# ttl-nixie-clock.net
KiCad netlist of a schematic drawn in EAGLE
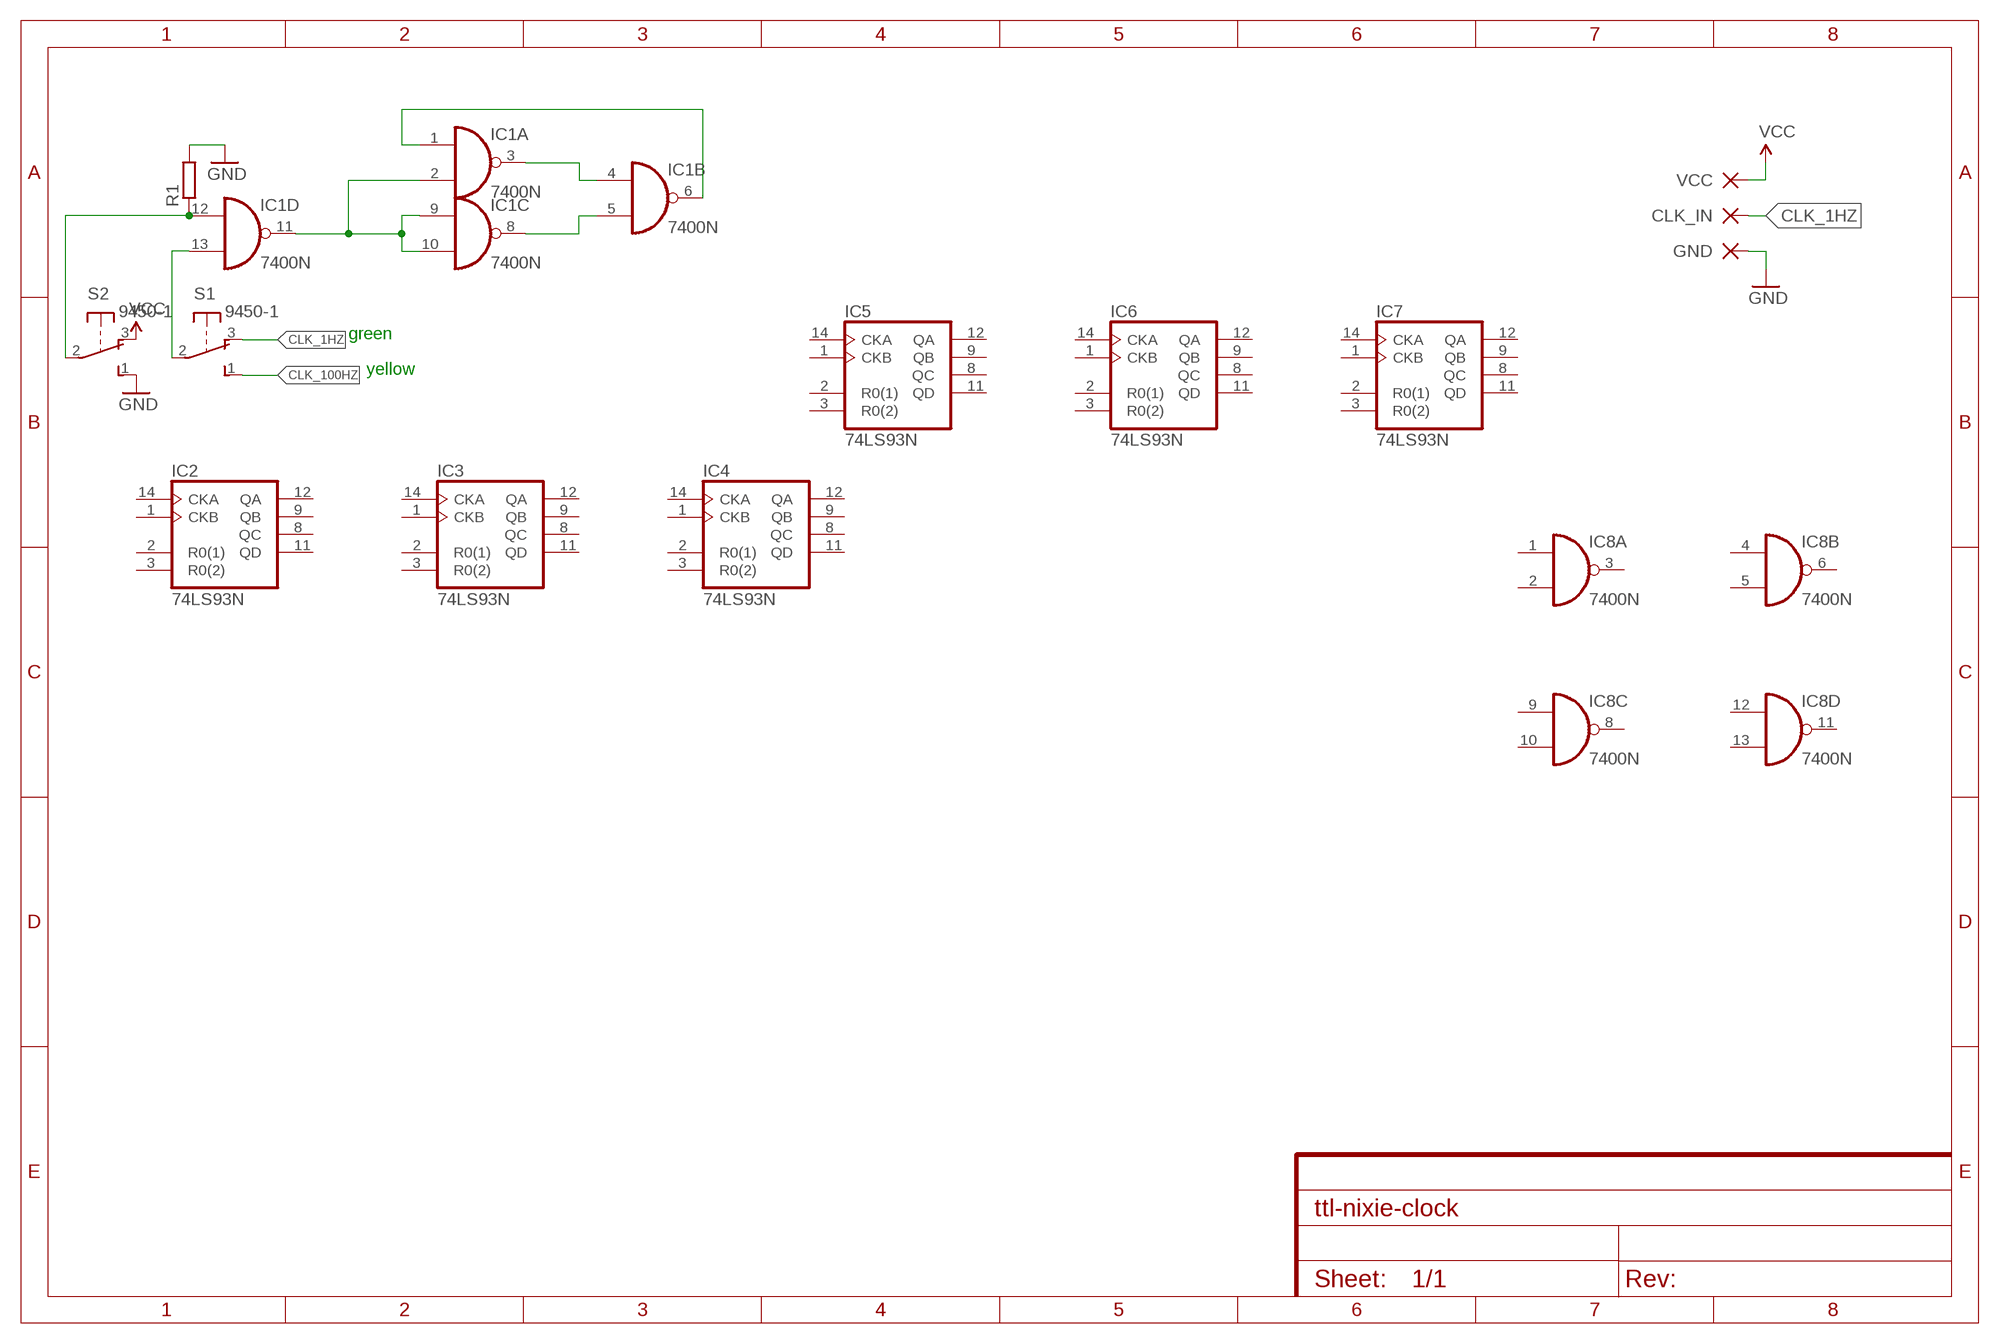
[diagram p0: schematic, sheet 1]

(export (version "E")
  (design (tool "Eeschema 10.0.6"))
  (components
    (comp (ref "CLK_IN")
      (value "CLK_OUT")
      (footprint "eagle-import:2,15_1,0")
      (libsource (lib "eagle-import") (part "2,15/1,0"))
    )
    (comp (ref "GND")
      (value "GND")
      (footprint "eagle-import:2,15_1,0")
      (libsource (lib "eagle-import") (part "2,15/1,0"))
    )
    (comp (ref "IC1")
      (value "7400N")
      (footprint "eagle-import:DIL14")
      (libsource (lib "eagle-import") (part "7400N"))
    )
    (comp (ref "IC2")
      (value "74LS93N")
      (footprint "eagle-import:DIL14")
      (libsource (lib "eagle-import") (part "7493NLS"))
    )
    (comp (ref "IC3")
      (value "74LS93N")
      (footprint "eagle-import:DIL14")
      (libsource (lib "eagle-import") (part "7493NLS"))
    )
    (comp (ref "IC4")
      (value "74LS93N")
      (footprint "eagle-import:DIL14")
      (libsource (lib "eagle-import") (part "7493NLS"))
    )
    (comp (ref "IC5")
      (value "74LS93N")
      (footprint "eagle-import:DIL14")
      (libsource (lib "eagle-import") (part "7493NLS"))
    )
    (comp (ref "IC6")
      (value "74LS93N")
      (footprint "eagle-import:DIL14")
      (libsource (lib "eagle-import") (part "7493NLS"))
    )
    (comp (ref "IC7")
      (value "74LS93N")
      (footprint "eagle-import:DIL14")
      (libsource (lib "eagle-import") (part "7493NLS"))
    )
    (comp (ref "IC8")
      (value "7400N")
      (footprint "eagle-import:DIL14")
      (libsource (lib "eagle-import") (part "7400N"))
    )
    (comp (ref "R1")
      (value "R-EU_0207/12")
      (footprint "eagle-import:0207_12")
      (libsource (lib "eagle-import") (part "R-EU_0207/12"))
    )
    (comp (ref "S1")
      (value "9450-1")
      (footprint "eagle-import:9450-1")
      (libsource (lib "eagle-import") (part "9450-1"))
    )
    (comp (ref "S2")
      (value "9450-1")
      (footprint "eagle-import:9450-1")
      (libsource (lib "eagle-import") (part "9450-1"))
    )
    (comp (ref "VCC")
      (value "VCC")
      (footprint "eagle-import:2,15_1,0")
      (libsource (lib "eagle-import") (part "2,15/1,0"))
    )
  )
  (nets
    (net (code "1") (name "CLK_1HZ") (class "Default")
      (node (ref "CLK_IN") (pin "1") (pinfunction "P_1") (pintype "passive"))
      (node (ref "S1") (pin "3") (pinfunction "O_3") (pintype "passive"))
    )
    (net (code "2") (name "CLK_100HZ") (class "Default")
      (node (ref "S1") (pin "1") (pinfunction "S_1") (pintype "passive"))
    )
    (net (code "3") (name "GND") (class "Default")
      (node (ref "GND") (pin "1") (pinfunction "P_1") (pintype "passive"))
      (node (ref "R1") (pin "2") (pinfunction "2_2") (pintype "passive"))
      (node (ref "S2") (pin "1") (pinfunction "S_1") (pintype "passive"))
    )
    (net (code "4") (name "Net-(IC1A-I0)") (class "Default")
      (node (ref "IC1") (pin "1") (pinfunction "I0_1") (pintype "input"))
      (node (ref "IC1") (pin "6") (pinfunction "O_6") (pintype "output"))
    )
    (net (code "5") (name "Net-(IC1A-I1)") (class "Default")
      (node (ref "IC1") (pin "10") (pinfunction "I1_10") (pintype "input"))
      (node (ref "IC1") (pin "11") (pinfunction "O_11") (pintype "output"))
      (node (ref "IC1") (pin "2") (pinfunction "I1_2") (pintype "input"))
      (node (ref "IC1") (pin "9") (pinfunction "I0_9") (pintype "input"))
    )
    (net (code "6") (name "Net-(IC1A-O)") (class "Default")
      (node (ref "IC1") (pin "3") (pinfunction "O_3") (pintype "output"))
      (node (ref "IC1") (pin "4") (pinfunction "I0_4") (pintype "input"))
    )
    (net (code "7") (name "Net-(IC1B-I1)") (class "Default")
      (node (ref "IC1") (pin "5") (pinfunction "I1_5") (pintype "input"))
      (node (ref "IC1") (pin "8") (pinfunction "O_8") (pintype "output"))
    )
    (net (code "8") (name "Net-(IC1D-I0)") (class "Default")
      (node (ref "IC1") (pin "12") (pinfunction "I0_12") (pintype "input"))
      (node (ref "R1") (pin "1") (pinfunction "1_1") (pintype "passive"))
      (node (ref "S2") (pin "2") (pinfunction "P_2") (pintype "passive"))
    )
    (net (code "9") (name "Net-(IC1D-I1)") (class "Default")
      (node (ref "IC1") (pin "13") (pinfunction "I1_13") (pintype "input"))
      (node (ref "S1") (pin "2") (pinfunction "P_2") (pintype "passive"))
    )
    (net (code "10") (name "VCC") (class "Default")
      (node (ref "S2") (pin "3") (pinfunction "O_3") (pintype "passive"))
      (node (ref "VCC") (pin "1") (pinfunction "P_1") (pintype "passive"))
    )
    (net (code "11") (name "unconnected-(IC2A-CKA-Pad14)") (class "Default")
      (node (ref "IC2") (pin "14") (pinfunction "CKA_14") (pintype "input"))
    )
    (net (code "12") (name "unconnected-(IC2A-CKB-Pad1)") (class "Default")
      (node (ref "IC2") (pin "1") (pinfunction "CKB_1") (pintype "input"))
    )
    (net (code "13") (name "unconnected-(IC2A-QA-Pad12)") (class "Default")
      (node (ref "IC2") (pin "12") (pinfunction "QA_12") (pintype "output"))
    )
    (net (code "14") (name "unconnected-(IC2A-QB-Pad9)") (class "Default")
      (node (ref "IC2") (pin "9") (pinfunction "QB_9") (pintype "output"))
    )
    (net (code "15") (name "unconnected-(IC2A-QC-Pad8)") (class "Default")
      (node (ref "IC2") (pin "8") (pinfunction "QC_8") (pintype "output"))
    )
    (net (code "16") (name "unconnected-(IC2A-QD-Pad11)") (class "Default")
      (node (ref "IC2") (pin "11") (pinfunction "QD_11") (pintype "output"))
    )
    (net (code "17") (name "unconnected-(IC2A-R0(1)-Pad2)") (class "Default")
      (node (ref "IC2") (pin "2") (pinfunction "R0(1)_2") (pintype "input"))
    )
    (net (code "18") (name "unconnected-(IC2A-R0(2)-Pad3)") (class "Default")
      (node (ref "IC2") (pin "3") (pinfunction "R0(2)_3") (pintype "input"))
    )
    (net (code "19") (name "unconnected-(IC3A-CKA-Pad14)") (class "Default")
      (node (ref "IC3") (pin "14") (pinfunction "CKA_14") (pintype "input"))
    )
    (net (code "20") (name "unconnected-(IC3A-CKB-Pad1)") (class "Default")
      (node (ref "IC3") (pin "1") (pinfunction "CKB_1") (pintype "input"))
    )
    (net (code "21") (name "unconnected-(IC3A-QA-Pad12)") (class "Default")
      (node (ref "IC3") (pin "12") (pinfunction "QA_12") (pintype "output"))
    )
    (net (code "22") (name "unconnected-(IC3A-QB-Pad9)") (class "Default")
      (node (ref "IC3") (pin "9") (pinfunction "QB_9") (pintype "output"))
    )
    (net (code "23") (name "unconnected-(IC3A-QC-Pad8)") (class "Default")
      (node (ref "IC3") (pin "8") (pinfunction "QC_8") (pintype "output"))
    )
    (net (code "24") (name "unconnected-(IC3A-QD-Pad11)") (class "Default")
      (node (ref "IC3") (pin "11") (pinfunction "QD_11") (pintype "output"))
    )
    (net (code "25") (name "unconnected-(IC3A-R0(1)-Pad2)") (class "Default")
      (node (ref "IC3") (pin "2") (pinfunction "R0(1)_2") (pintype "input"))
    )
    (net (code "26") (name "unconnected-(IC3A-R0(2)-Pad3)") (class "Default")
      (node (ref "IC3") (pin "3") (pinfunction "R0(2)_3") (pintype "input"))
    )
    (net (code "27") (name "unconnected-(IC4A-CKA-Pad14)") (class "Default")
      (node (ref "IC4") (pin "14") (pinfunction "CKA_14") (pintype "input"))
    )
    (net (code "28") (name "unconnected-(IC4A-CKB-Pad1)") (class "Default")
      (node (ref "IC4") (pin "1") (pinfunction "CKB_1") (pintype "input"))
    )
    (net (code "29") (name "unconnected-(IC4A-QA-Pad12)") (class "Default")
      (node (ref "IC4") (pin "12") (pinfunction "QA_12") (pintype "output"))
    )
    (net (code "30") (name "unconnected-(IC4A-QB-Pad9)") (class "Default")
      (node (ref "IC4") (pin "9") (pinfunction "QB_9") (pintype "output"))
    )
    (net (code "31") (name "unconnected-(IC4A-QC-Pad8)") (class "Default")
      (node (ref "IC4") (pin "8") (pinfunction "QC_8") (pintype "output"))
    )
    (net (code "32") (name "unconnected-(IC4A-QD-Pad11)") (class "Default")
      (node (ref "IC4") (pin "11") (pinfunction "QD_11") (pintype "output"))
    )
    (net (code "33") (name "unconnected-(IC4A-R0(1)-Pad2)") (class "Default")
      (node (ref "IC4") (pin "2") (pinfunction "R0(1)_2") (pintype "input"))
    )
    (net (code "34") (name "unconnected-(IC4A-R0(2)-Pad3)") (class "Default")
      (node (ref "IC4") (pin "3") (pinfunction "R0(2)_3") (pintype "input"))
    )
    (net (code "35") (name "unconnected-(IC5A-CKA-Pad14)") (class "Default")
      (node (ref "IC5") (pin "14") (pinfunction "CKA_14") (pintype "input"))
    )
    (net (code "36") (name "unconnected-(IC5A-CKB-Pad1)") (class "Default")
      (node (ref "IC5") (pin "1") (pinfunction "CKB_1") (pintype "input"))
    )
    (net (code "37") (name "unconnected-(IC5A-QA-Pad12)") (class "Default")
      (node (ref "IC5") (pin "12") (pinfunction "QA_12") (pintype "output"))
    )
    (net (code "38") (name "unconnected-(IC5A-QB-Pad9)") (class "Default")
      (node (ref "IC5") (pin "9") (pinfunction "QB_9") (pintype "output"))
    )
    (net (code "39") (name "unconnected-(IC5A-QC-Pad8)") (class "Default")
      (node (ref "IC5") (pin "8") (pinfunction "QC_8") (pintype "output"))
    )
    (net (code "40") (name "unconnected-(IC5A-QD-Pad11)") (class "Default")
      (node (ref "IC5") (pin "11") (pinfunction "QD_11") (pintype "output"))
    )
    (net (code "41") (name "unconnected-(IC5A-R0(1)-Pad2)") (class "Default")
      (node (ref "IC5") (pin "2") (pinfunction "R0(1)_2") (pintype "input"))
    )
    (net (code "42") (name "unconnected-(IC5A-R0(2)-Pad3)") (class "Default")
      (node (ref "IC5") (pin "3") (pinfunction "R0(2)_3") (pintype "input"))
    )
    (net (code "43") (name "unconnected-(IC6A-CKA-Pad14)") (class "Default")
      (node (ref "IC6") (pin "14") (pinfunction "CKA_14") (pintype "input"))
    )
    (net (code "44") (name "unconnected-(IC6A-CKB-Pad1)") (class "Default")
      (node (ref "IC6") (pin "1") (pinfunction "CKB_1") (pintype "input"))
    )
    (net (code "45") (name "unconnected-(IC6A-QA-Pad12)") (class "Default")
      (node (ref "IC6") (pin "12") (pinfunction "QA_12") (pintype "output"))
    )
    (net (code "46") (name "unconnected-(IC6A-QB-Pad9)") (class "Default")
      (node (ref "IC6") (pin "9") (pinfunction "QB_9") (pintype "output"))
    )
    (net (code "47") (name "unconnected-(IC6A-QC-Pad8)") (class "Default")
      (node (ref "IC6") (pin "8") (pinfunction "QC_8") (pintype "output"))
    )
    (net (code "48") (name "unconnected-(IC6A-QD-Pad11)") (class "Default")
      (node (ref "IC6") (pin "11") (pinfunction "QD_11") (pintype "output"))
    )
    (net (code "49") (name "unconnected-(IC6A-R0(1)-Pad2)") (class "Default")
      (node (ref "IC6") (pin "2") (pinfunction "R0(1)_2") (pintype "input"))
    )
    (net (code "50") (name "unconnected-(IC6A-R0(2)-Pad3)") (class "Default")
      (node (ref "IC6") (pin "3") (pinfunction "R0(2)_3") (pintype "input"))
    )
    (net (code "51") (name "unconnected-(IC7A-CKA-Pad14)") (class "Default")
      (node (ref "IC7") (pin "14") (pinfunction "CKA_14") (pintype "input"))
    )
    (net (code "52") (name "unconnected-(IC7A-CKB-Pad1)") (class "Default")
      (node (ref "IC7") (pin "1") (pinfunction "CKB_1") (pintype "input"))
    )
    (net (code "53") (name "unconnected-(IC7A-QA-Pad12)") (class "Default")
      (node (ref "IC7") (pin "12") (pinfunction "QA_12") (pintype "output"))
    )
    (net (code "54") (name "unconnected-(IC7A-QB-Pad9)") (class "Default")
      (node (ref "IC7") (pin "9") (pinfunction "QB_9") (pintype "output"))
    )
    (net (code "55") (name "unconnected-(IC7A-QC-Pad8)") (class "Default")
      (node (ref "IC7") (pin "8") (pinfunction "QC_8") (pintype "output"))
    )
    (net (code "56") (name "unconnected-(IC7A-QD-Pad11)") (class "Default")
      (node (ref "IC7") (pin "11") (pinfunction "QD_11") (pintype "output"))
    )
    (net (code "57") (name "unconnected-(IC7A-R0(1)-Pad2)") (class "Default")
      (node (ref "IC7") (pin "2") (pinfunction "R0(1)_2") (pintype "input"))
    )
    (net (code "58") (name "unconnected-(IC7A-R0(2)-Pad3)") (class "Default")
      (node (ref "IC7") (pin "3") (pinfunction "R0(2)_3") (pintype "input"))
    )
    (net (code "59") (name "unconnected-(IC8A-I0-Pad1)") (class "Default")
      (node (ref "IC8") (pin "1") (pinfunction "I0_1") (pintype "input"))
    )
    (net (code "60") (name "unconnected-(IC8A-I1-Pad2)") (class "Default")
      (node (ref "IC8") (pin "2") (pinfunction "I1_2") (pintype "input"))
    )
    (net (code "61") (name "unconnected-(IC8A-O-Pad3)") (class "Default")
      (node (ref "IC8") (pin "3") (pinfunction "O_3") (pintype "output"))
    )
    (net (code "62") (name "unconnected-(IC8B-I0-Pad4)") (class "Default")
      (node (ref "IC8") (pin "4") (pinfunction "I0_4") (pintype "input"))
    )
    (net (code "63") (name "unconnected-(IC8B-I1-Pad5)") (class "Default")
      (node (ref "IC8") (pin "5") (pinfunction "I1_5") (pintype "input"))
    )
    (net (code "64") (name "unconnected-(IC8B-O-Pad6)") (class "Default")
      (node (ref "IC8") (pin "6") (pinfunction "O_6") (pintype "output"))
    )
    (net (code "65") (name "unconnected-(IC8C-I0-Pad9)") (class "Default")
      (node (ref "IC8") (pin "9") (pinfunction "I0_9") (pintype "input"))
    )
    (net (code "66") (name "unconnected-(IC8C-I1-Pad10)") (class "Default")
      (node (ref "IC8") (pin "10") (pinfunction "I1_10") (pintype "input"))
    )
    (net (code "67") (name "unconnected-(IC8C-O-Pad8)") (class "Default")
      (node (ref "IC8") (pin "8") (pinfunction "O_8") (pintype "output"))
    )
    (net (code "68") (name "unconnected-(IC8D-I0-Pad12)") (class "Default")
      (node (ref "IC8") (pin "12") (pinfunction "I0_12") (pintype "input"))
    )
    (net (code "69") (name "unconnected-(IC8D-I1-Pad13)") (class "Default")
      (node (ref "IC8") (pin "13") (pinfunction "I1_13") (pintype "input"))
    )
    (net (code "70") (name "unconnected-(IC8D-O-Pad11)") (class "Default")
      (node (ref "IC8") (pin "11") (pinfunction "O_11") (pintype "output"))
    )
  )
)
